# Shield_RTC_MCP7940N.net
KiCad netlist of a schematic drawn in EAGLE
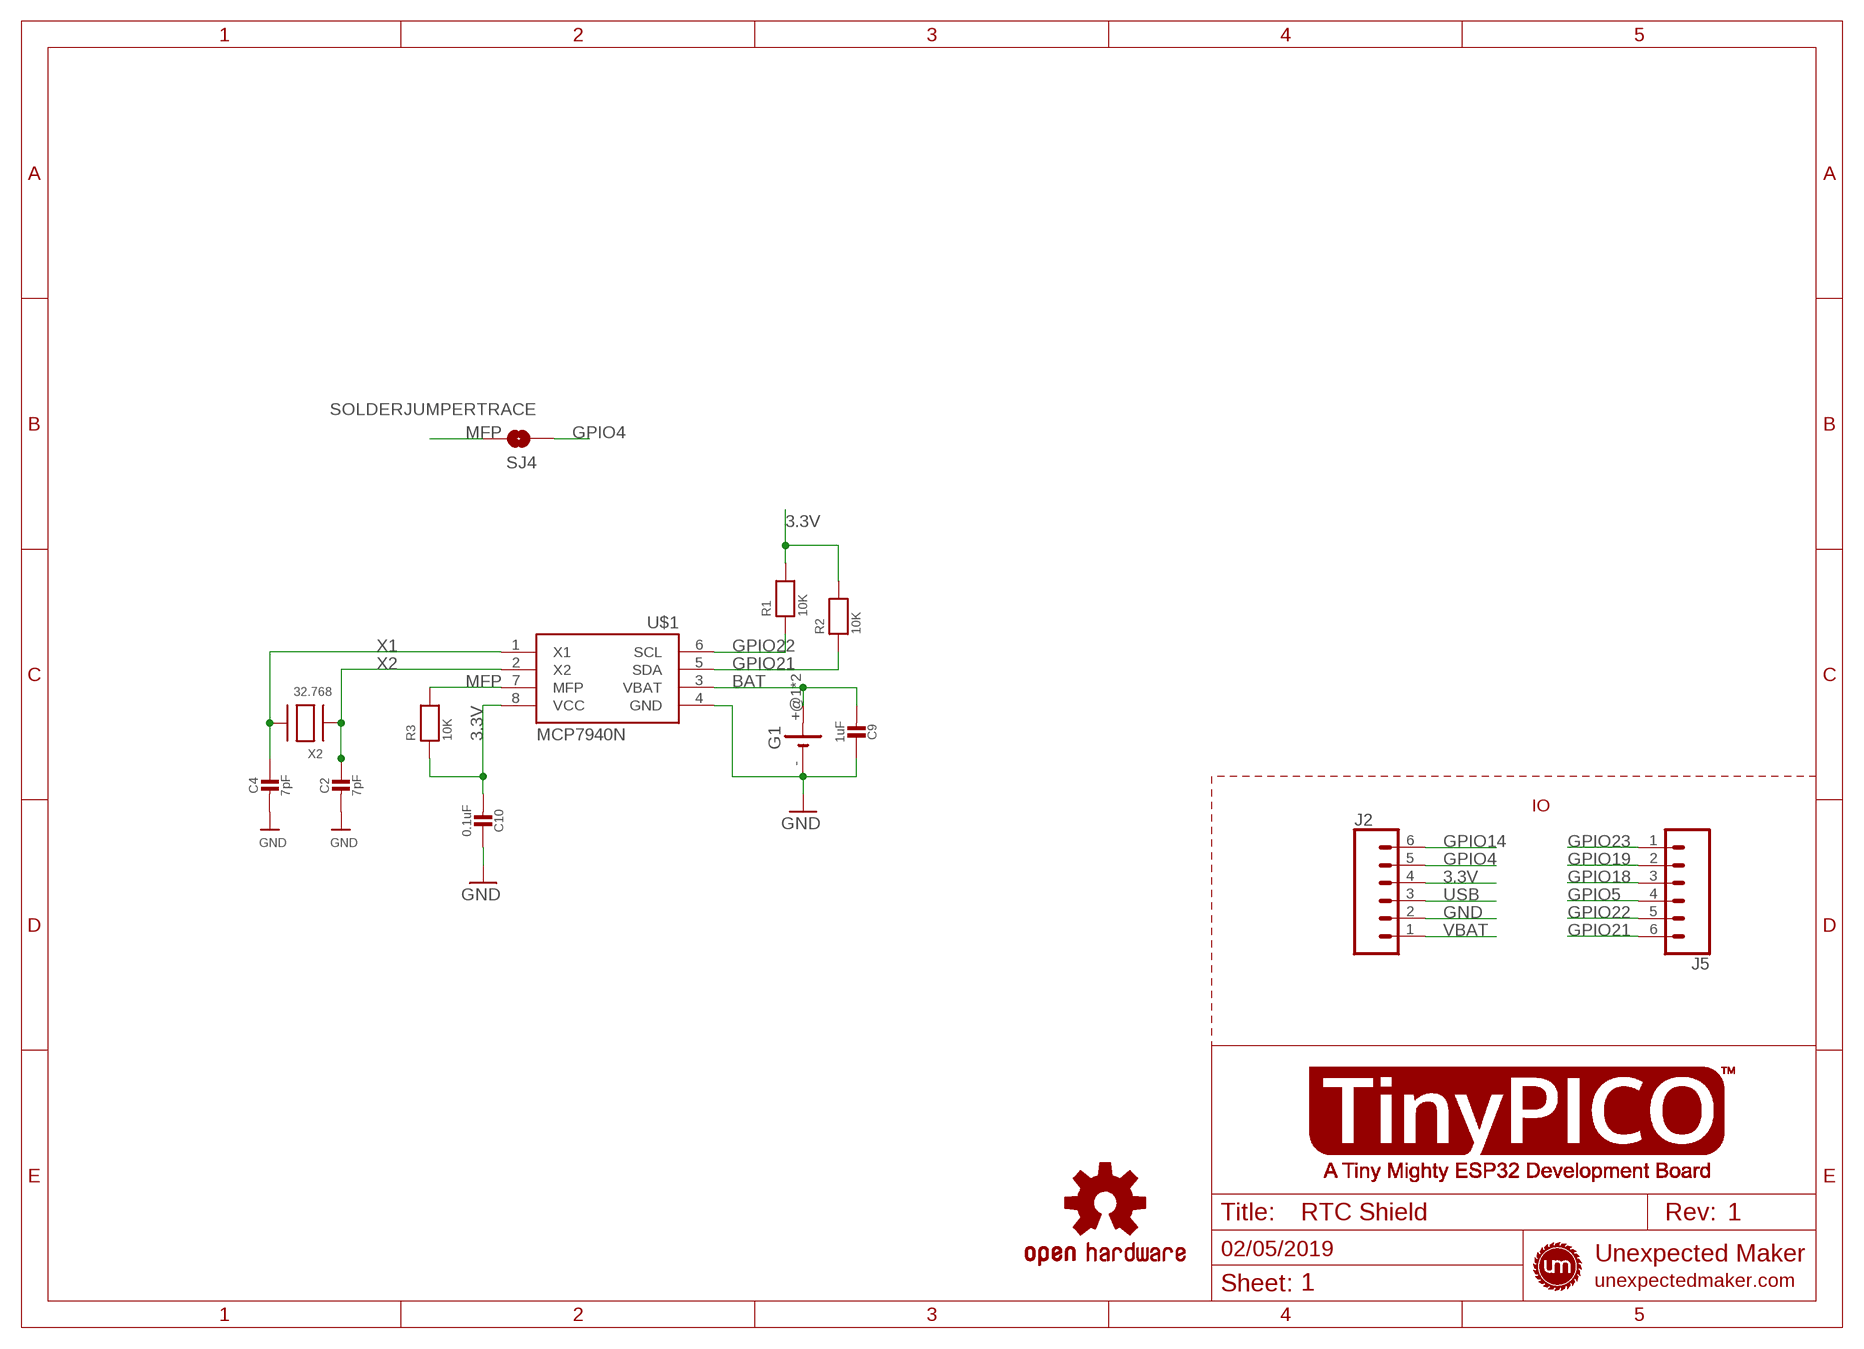
[diagram p0: schematic, sheet 1]

(export (version "E")
  (design (tool "Eeschema 10.0.6"))
  (components
    (comp (ref "C2")
      (value "7pF")
      (footprint "eagle-import:_0603MP")
      (libsource (lib "eagle-import") (part "CAP_CERAMIC_0603MP"))
    )
    (comp (ref "C4")
      (value "7pF")
      (footprint "eagle-import:_0603MP")
      (libsource (lib "eagle-import") (part "CAP_CERAMIC_0603MP"))
    )
    (comp (ref "C9")
      (value "1uF")
      (footprint "eagle-import:_0603MP")
      (libsource (lib "eagle-import") (part "CAP_CERAMIC_0603MP"))
    )
    (comp (ref "C10")
      (value "0.1uF")
      (footprint "eagle-import:_0603MP")
      (libsource (lib "eagle-import") (part "CAP_CERAMIC_0603MP"))
    )
    (comp (ref "G1")
      (value "10MM_SM_COIN_CELL_CLIP")
      (footprint "eagle-import:10MM_SM_COIN_CELL_CLIP")
      (libsource (lib "eagle-import") (part "10MM_SM_COIN_CELL_CLIP"))
    )
    (comp (ref "J2")
      (value "CONN_06NO_SILK_FEMALE_PTH")
      (footprint "eagle-import:1X06_NO_SILK")
      (libsource (lib "eagle-import") (part "CONN_06NO_SILK_FEMALE_PTH"))
    )
    (comp (ref "J5")
      (value "CONN_06NO_SILK_FEMALE_PTH")
      (footprint "eagle-import:1X06_NO_SILK")
      (libsource (lib "eagle-import") (part "CONN_06NO_SILK_FEMALE_PTH"))
    )
    (comp (ref "LOGO1")
      (value "OSHW-LOGOS")
      (footprint "eagle-import:OSHW-LOGO-S")
      (libsource (lib "eagle-import") (part "OSHW-LOGOS"))
    )
    (comp (ref "R1")
      (value "10K")
      (footprint "eagle-import:_0603MP")
      (libsource (lib "eagle-import") (part "RESISTOR_0603MP"))
    )
    (comp (ref "R2")
      (value "10K")
      (footprint "eagle-import:_0603MP")
      (libsource (lib "eagle-import") (part "RESISTOR_0603MP"))
    )
    (comp (ref "R3")
      (value "10K")
      (footprint "eagle-import:_0603MP")
      (libsource (lib "eagle-import") (part "RESISTOR_0603MP"))
    )
    (comp (ref "SJ4")
      (value "SOLDERJUMPERTRACE")
      (footprint "eagle-import:SPARKFUN_SJ_2S-TRACE")
      (libsource (lib "eagle-import") (part "SOLDERJUMPERTRACE"))
    )
    (comp (ref "U$1")
      (value "MCP7940N")
      (footprint "eagle-import:SOIC8_150MIL")
      (libsource (lib "eagle-import") (part "MCP7940N"))
    )
    (comp (ref "X2")
      (value "32.768")
      (footprint "eagle-import:XTAL3215")
      (libsource (lib "eagle-import") (part "XTAL-3.2X1.5"))
    )
  )
  (nets
    (net (code "1") (name "/3.3V") (class "Default")
      (node (ref "C10") (pin "2") (pinfunction "2_2") (pintype "passive"))
      (node (ref "J2") (pin "4") (pinfunction "4_4") (pintype "passive"))
      (node (ref "R1") (pin "2") (pinfunction "2_2") (pintype "passive"))
      (node (ref "R2") (pin "2") (pinfunction "2_2") (pintype "passive"))
      (node (ref "R3") (pin "1") (pinfunction "1_1") (pintype "passive"))
      (node (ref "U$1") (pin "8") (pinfunction "VCC_8") (pintype "passive"))
    )
    (net (code "2") (name "/BAT") (class "Default")
      (node (ref "C9") (pin "2") (pinfunction "2_2") (pintype "passive"))
      (node (ref "G1") (pin "+@1") (pinfunction "+_+@1") (pintype "passive"))
      (node (ref "G1") (pin "+@2") (pinfunction "+_+@2") (pintype "passive"))
      (node (ref "U$1") (pin "3") (pinfunction "VBAT_3") (pintype "power_in"))
    )
    (net (code "3") (name "/GPIO4") (class "Default")
      (node (ref "J2") (pin "5") (pinfunction "5_5") (pintype "passive"))
      (node (ref "SJ4") (pin "1") (pinfunction "1_1") (pintype "passive"))
    )
    (net (code "4") (name "/GPIO5") (class "Default")
      (node (ref "J5") (pin "4") (pinfunction "4_4") (pintype "passive"))
    )
    (net (code "5") (name "/GPIO14") (class "Default")
      (node (ref "J2") (pin "6") (pinfunction "6_6") (pintype "passive"))
    )
    (net (code "6") (name "/GPIO18") (class "Default")
      (node (ref "J5") (pin "3") (pinfunction "3_3") (pintype "passive"))
    )
    (net (code "7") (name "/GPIO19") (class "Default")
      (node (ref "J5") (pin "2") (pinfunction "2_2") (pintype "passive"))
    )
    (net (code "8") (name "/GPIO21") (class "Default")
      (node (ref "J5") (pin "6") (pinfunction "6_6") (pintype "passive"))
      (node (ref "R2") (pin "1") (pinfunction "1_1") (pintype "passive"))
      (node (ref "U$1") (pin "5") (pinfunction "SDA_5") (pintype "bidirectional"))
    )
    (net (code "9") (name "/GPIO22") (class "Default")
      (node (ref "J5") (pin "5") (pinfunction "5_5") (pintype "passive"))
      (node (ref "R1") (pin "1") (pinfunction "1_1") (pintype "passive"))
      (node (ref "U$1") (pin "6") (pinfunction "SCL_6") (pintype "bidirectional"))
    )
    (net (code "10") (name "/GPIO23") (class "Default")
      (node (ref "J5") (pin "1") (pinfunction "1_1") (pintype "passive"))
    )
    (net (code "11") (name "/MFP") (class "Default")
      (node (ref "R3") (pin "2") (pinfunction "2_2") (pintype "passive"))
      (node (ref "SJ4") (pin "2") (pinfunction "2_2") (pintype "passive"))
      (node (ref "U$1") (pin "7") (pinfunction "MFP_7") (pintype "output"))
    )
    (net (code "12") (name "/USB") (class "Default")
      (node (ref "J2") (pin "3") (pinfunction "3_3") (pintype "passive"))
    )
    (net (code "13") (name "/VBAT") (class "Default")
      (node (ref "J2") (pin "1") (pinfunction "1_1") (pintype "passive"))
    )
    (net (code "14") (name "/X1") (class "Default")
      (node (ref "C4") (pin "1") (pinfunction "1_1") (pintype "passive"))
      (node (ref "U$1") (pin "1") (pinfunction "X1_1") (pintype "output"))
      (node (ref "X2") (pin "P$2") (pinfunction "P$2_P$2") (pintype "bidirectional"))
    )
    (net (code "15") (name "/X2") (class "Default")
      (node (ref "C2") (pin "1") (pinfunction "1_1") (pintype "passive"))
      (node (ref "U$1") (pin "2") (pinfunction "X2_2") (pintype "power_in"))
      (node (ref "X2") (pin "P$1") (pinfunction "P$1_P$1") (pintype "bidirectional"))
    )
    (net (code "16") (name "GND") (class "Default")
      (node (ref "C10") (pin "1") (pinfunction "1_1") (pintype "passive"))
      (node (ref "C2") (pin "2") (pinfunction "2_2") (pintype "passive"))
      (node (ref "C4") (pin "2") (pinfunction "2_2") (pintype "passive"))
      (node (ref "C9") (pin "1") (pinfunction "1_1") (pintype "passive"))
      (node (ref "G1") (pin "-") (pinfunction "-_-") (pintype "passive"))
      (node (ref "J2") (pin "2") (pinfunction "2_2") (pintype "passive"))
      (node (ref "U$1") (pin "4") (pinfunction "GND_4") (pintype "power_in"))
    )
  )
)
